# 12V_to_6V_isolated_LM3478.net
KiCad netlist of a schematic drawn in EAGLE
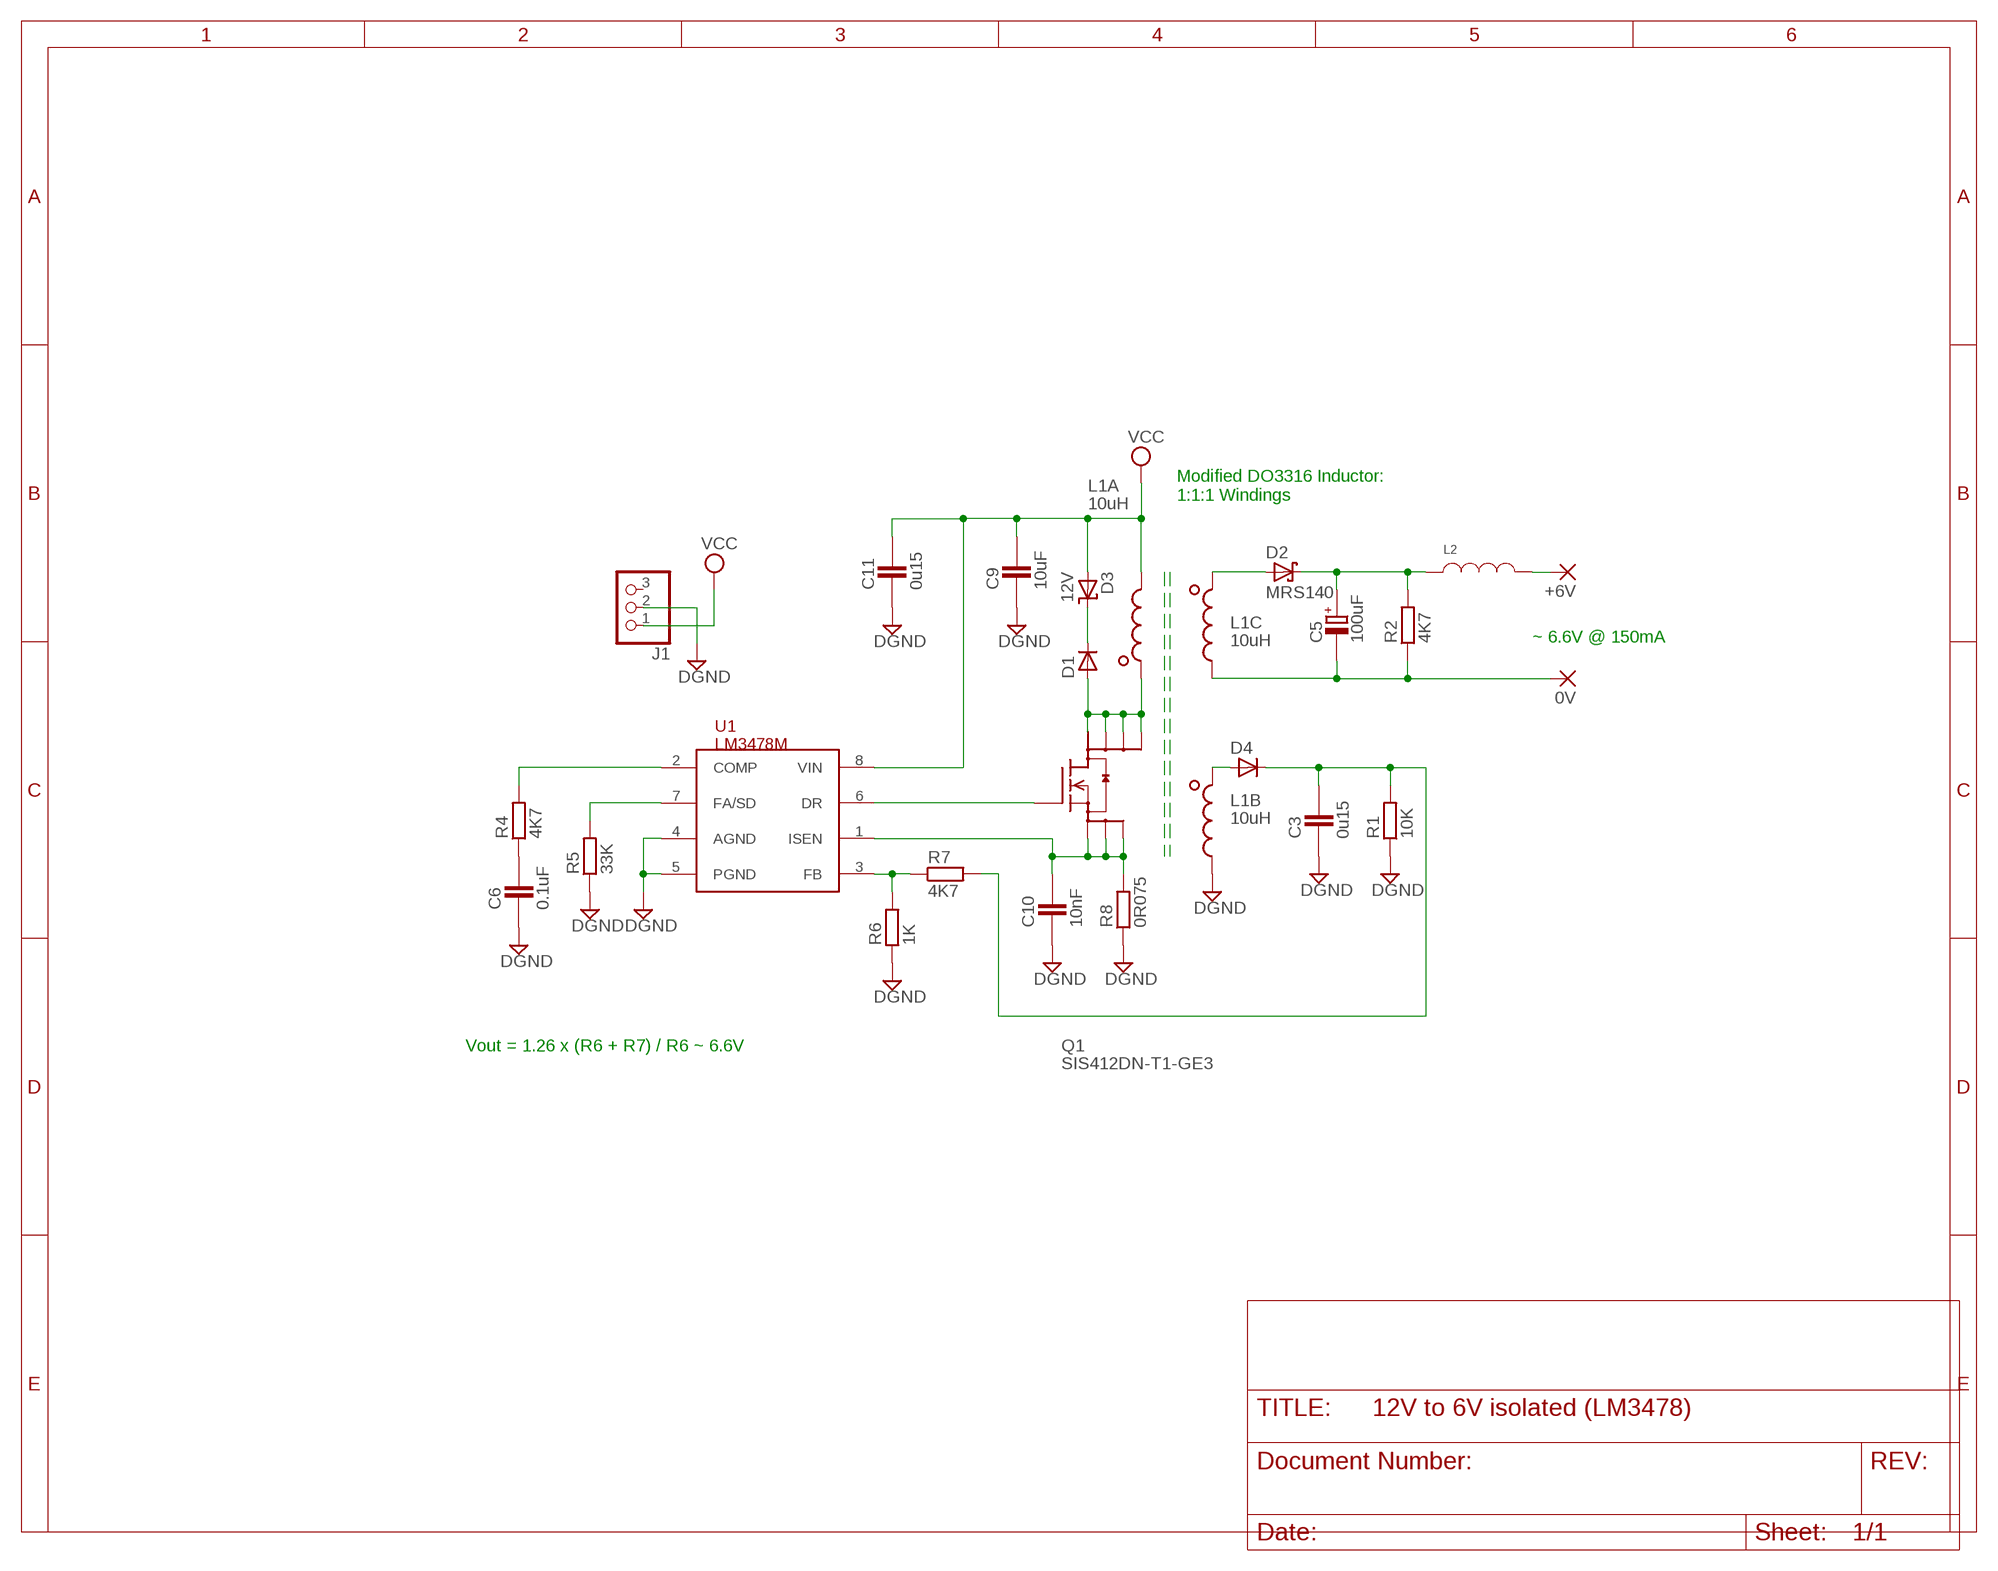
[diagram p0: schematic, sheet 1]

(export (version "E")
  (design (tool "Eeschema 10.0.6"))
  (components
    (comp (ref "+6V")
      (value "SMD2")
      (footprint "eagle-import:SMD1,27-2,54")
      (libsource (lib "eagle-import") (part "SMD2"))
    )
    (comp (ref "0V")
      (value "SMD2")
      (footprint "eagle-import:SMD1,27-2,54")
      (libsource (lib "eagle-import") (part "SMD2"))
    )
    (comp (ref "C3")
      (value "0u15")
      (footprint "eagle-import:CAP2012X70N")
      (libsource (lib "eagle-import") (part "CAPACITOR_0805N"))
    )
    (comp (ref "C5")
      (value "100uF")
      (footprint "eagle-import:CAPMP7343X310N")
      (libsource (lib "eagle-import") (part "POLARISED_D_CASE"))
    )
    (comp (ref "C6")
      (value "0.1uF")
      (footprint "eagle-import:CAPC1608X92N")
      (libsource (lib "eagle-import") (part "CAPACITOR_0603"))
    )
    (comp (ref "C9")
      (value "10uF")
      (footprint "eagle-import:CAPC3225X168N")
      (libsource (lib "eagle-import") (part "CAPACITOR_1210"))
    )
    (comp (ref "C10")
      (value "10nF")
      (footprint "eagle-import:CAPC1608X92N")
      (libsource (lib "eagle-import") (part "CAPACITOR_0603"))
    )
    (comp (ref "C11")
      (value "0u15")
      (footprint "eagle-import:CAP2012X70N")
      (libsource (lib "eagle-import") (part "CAPACITOR_0805N"))
    )
    (comp (ref "D1")
      (value "DIODE_SOT-23")
      (footprint "eagle-import:SOT95P280X135-3N")
      (libsource (lib "eagle-import") (part "DIODE_SOT-23"))
    )
    (comp (ref "D2")
      (value "MRS140")
      (footprint "eagle-import:DIOM5436X265N")
      (libsource (lib "eagle-import") (part "SCHOTTKY_SMB"))
    )
    (comp (ref "D3")
      (value "12V")
      (footprint "eagle-import:SOT95P280X135-3N")
      (libsource (lib "eagle-import") (part "ZENER_SOT-23"))
    )
    (comp (ref "D4")
      (value "DIODE_SOT-23")
      (footprint "eagle-import:SOT95P280X135-3N")
      (libsource (lib "eagle-import") (part "DIODE_SOT-23"))
    )
    (comp (ref "J1")
      (value "PINHD-1X3")
      (footprint "eagle-import:1X03")
      (libsource (lib "eagle-import") (part "PINHD-1X3"))
    )
    (comp (ref "L1")
      (value "10uH")
      (footprint "eagle-import:DO3316P-3")
      (libsource (lib "eagle-import") (part "DO3316P-3"))
    )
    (comp (ref "L2")
      (value "INDUCTOR_1812")
      (footprint "eagle-import:INDC4532X175N")
      (libsource (lib "eagle-import") (part "INDUCTOR_1812"))
    )
    (comp (ref "Q1")
      (value "SIS412DN-T1-GE3")
      (footprint "eagle-import:POWER-PAK1212")
      (libsource (lib "eagle-import") (part "MOSFET-NCH_8_1212"))
    )
    (comp (ref "R1")
      (value "10K")
      (footprint "eagle-import:RESC2012X70N")
      (libsource (lib "eagle-import") (part "RESISTOR_0805"))
    )
    (comp (ref "R2")
      (value "4K7")
      (footprint "eagle-import:RESC2012X70N")
      (libsource (lib "eagle-import") (part "RESISTOR_0805"))
    )
    (comp (ref "R4")
      (value "4K7")
      (footprint "eagle-import:RESC1608X55N")
      (libsource (lib "eagle-import") (part "RESISTOR_0603"))
    )
    (comp (ref "R5")
      (value "33K")
      (footprint "eagle-import:RESC1608X55N")
      (libsource (lib "eagle-import") (part "RESISTOR_0603"))
    )
    (comp (ref "R6")
      (value "1K")
      (footprint "eagle-import:RESC2012X70N")
      (libsource (lib "eagle-import") (part "RESISTOR_0805"))
    )
    (comp (ref "R7")
      (value "4K7")
      (footprint "eagle-import:RESC2012X70N")
      (libsource (lib "eagle-import") (part "RESISTOR_0805"))
    )
    (comp (ref "R8")
      (value "0R075")
      (footprint "eagle-import:RESC6432X70N")
      (libsource (lib "eagle-import") (part "RESISTOR_2512"))
    )
    (comp (ref "U1")
      (value "LM3478M")
      (footprint "eagle-import:MSOP8")
      (libsource (lib "eagle-import") (part "LM3478M"))
    )
  )
  (nets
    (net (code "1") (name "DGND") (class "Default")
      (node (ref "C10") (pin "1") (pinfunction "1_1") (pintype "passive"))
      (node (ref "C11") (pin "1") (pinfunction "1_1") (pintype "passive"))
      (node (ref "C3") (pin "1") (pinfunction "1_1") (pintype "passive"))
      (node (ref "C6") (pin "1") (pinfunction "1_1") (pintype "passive"))
      (node (ref "C9") (pin "1") (pinfunction "1_1") (pintype "passive"))
      (node (ref "J1") (pin "2") (pinfunction "2_2") (pintype "passive"))
      (node (ref "L1") (pin "4") (pinfunction "2_4") (pintype "passive"))
      (node (ref "R1") (pin "1") (pinfunction "1_1") (pintype "passive"))
      (node (ref "R5") (pin "1") (pinfunction "1_1") (pintype "passive"))
      (node (ref "R6") (pin "1") (pinfunction "1_1") (pintype "passive"))
      (node (ref "R8") (pin "1") (pinfunction "1_1") (pintype "passive"))
      (node (ref "U1") (pin "4") (pinfunction "AGND_4") (pintype "bidirectional"))
      (node (ref "U1") (pin "5") (pinfunction "PGND_5") (pintype "bidirectional"))
    )
    (net (code "2") (name "Net-(+6V-P)") (class "Default")
      (node (ref "+6V") (pin "1") (pinfunction "P_1") (pintype "passive"))
      (node (ref "L2") (pin "2") (pinfunction "2_2") (pintype "passive"))
    )
    (net (code "3") (name "Net-(0V-P)") (class "Default")
      (node (ref "0V") (pin "1") (pinfunction "P_1") (pintype "passive"))
      (node (ref "C5") (pin "-") (pinfunction "-_-") (pintype "passive"))
      (node (ref "L1") (pin "6") (pinfunction "2_6") (pintype "passive"))
      (node (ref "R2") (pin "1") (pinfunction "1_1") (pintype "passive"))
    )
    (net (code "4") (name "Net-(C5-Pad+)") (class "Default")
      (node (ref "C5") (pin "+") (pinfunction "+_+") (pintype "passive"))
      (node (ref "D2") (pin "K") (pinfunction "K_K") (pintype "passive"))
      (node (ref "L2") (pin "1") (pinfunction "1_1") (pintype "passive"))
      (node (ref "R2") (pin "2") (pinfunction "2_2") (pintype "passive"))
    )
    (net (code "5") (name "Net-(C6-Pad2)") (class "Default")
      (node (ref "C6") (pin "2") (pinfunction "2_2") (pintype "passive"))
      (node (ref "R4") (pin "1") (pinfunction "1_1") (pintype "passive"))
    )
    (net (code "6") (name "Net-(D1-A)") (class "Default")
      (node (ref "D1") (pin "1") (pinfunction "A_1") (pintype "passive"))
      (node (ref "L1") (pin "1") (pinfunction "1_1") (pintype "passive"))
      (node (ref "Q1") (pin "5") (pinfunction "D1_5") (pintype "passive"))
      (node (ref "Q1") (pin "6") (pinfunction "D2_6") (pintype "passive"))
      (node (ref "Q1") (pin "7") (pinfunction "D3_7") (pintype "passive"))
      (node (ref "Q1") (pin "8") (pinfunction "D4_8") (pintype "passive"))
    )
    (net (code "7") (name "Net-(D1-K)") (class "Default")
      (node (ref "D1") (pin "3") (pinfunction "K_3") (pintype "passive"))
      (node (ref "D3") (pin "3") (pinfunction "K_3") (pintype "passive"))
    )
    (net (code "8") (name "Net-(D4-A)") (class "Default")
      (node (ref "D4") (pin "1") (pinfunction "A_1") (pintype "passive"))
      (node (ref "L1") (pin "3") (pinfunction "1_3") (pintype "passive"))
    )
    (net (code "9") (name "Net-(D4-K)") (class "Default")
      (node (ref "C3") (pin "2") (pinfunction "2_2") (pintype "passive"))
      (node (ref "D4") (pin "3") (pinfunction "K_3") (pintype "passive"))
      (node (ref "R1") (pin "2") (pinfunction "2_2") (pintype "passive"))
      (node (ref "R7") (pin "2") (pinfunction "2_2") (pintype "passive"))
    )
    (net (code "10") (name "Net-(L1C-1)") (class "Default")
      (node (ref "D2") (pin "A") (pinfunction "A_A") (pintype "passive"))
      (node (ref "L1") (pin "5") (pinfunction "1_5") (pintype "passive"))
    )
    (net (code "11") (name "Net-(Q1-G)") (class "Default")
      (node (ref "Q1") (pin "4") (pinfunction "G_4") (pintype "passive"))
      (node (ref "U1") (pin "6") (pinfunction "DR_6") (pintype "bidirectional"))
    )
    (net (code "12") (name "Net-(Q1-S1)") (class "Default")
      (node (ref "C10") (pin "2") (pinfunction "2_2") (pintype "passive"))
      (node (ref "Q1") (pin "1") (pinfunction "S1_1") (pintype "passive"))
      (node (ref "Q1") (pin "2") (pinfunction "S2_2") (pintype "passive"))
      (node (ref "Q1") (pin "3") (pinfunction "S3_3") (pintype "passive"))
      (node (ref "R8") (pin "2") (pinfunction "2_2") (pintype "passive"))
      (node (ref "U1") (pin "1") (pinfunction "ISEN_1") (pintype "bidirectional"))
    )
    (net (code "13") (name "Net-(U1-COMP)") (class "Default")
      (node (ref "R4") (pin "2") (pinfunction "2_2") (pintype "passive"))
      (node (ref "U1") (pin "2") (pinfunction "COMP_2") (pintype "bidirectional"))
    )
    (net (code "14") (name "Net-(U1-FA{slash}SD)") (class "Default")
      (node (ref "R5") (pin "2") (pinfunction "2_2") (pintype "passive"))
      (node (ref "U1") (pin "7") (pinfunction "FA/SD_7") (pintype "bidirectional"))
    )
    (net (code "15") (name "Net-(U1-FB)") (class "Default")
      (node (ref "R6") (pin "2") (pinfunction "2_2") (pintype "passive"))
      (node (ref "R7") (pin "1") (pinfunction "1_1") (pintype "passive"))
      (node (ref "U1") (pin "3") (pinfunction "FB_3") (pintype "bidirectional"))
    )
    (net (code "16") (name "VCC") (class "Default")
      (node (ref "C11") (pin "2") (pinfunction "2_2") (pintype "passive"))
      (node (ref "C9") (pin "2") (pinfunction "2_2") (pintype "passive"))
      (node (ref "D3") (pin "1") (pinfunction "A_1") (pintype "passive"))
      (node (ref "J1") (pin "1") (pinfunction "1_1") (pintype "passive"))
      (node (ref "L1") (pin "2") (pinfunction "2_2") (pintype "passive"))
      (node (ref "U1") (pin "8") (pinfunction "VIN_8") (pintype "bidirectional"))
    )
    (net (code "17") (name "unconnected-(J1-Pad3)") (class "Default")
      (node (ref "J1") (pin "3") (pinfunction "3_3") (pintype "passive"))
    )
  )
)
